# navx_micro_1_0.net
KiCad netlist of a schematic drawn in EAGLE
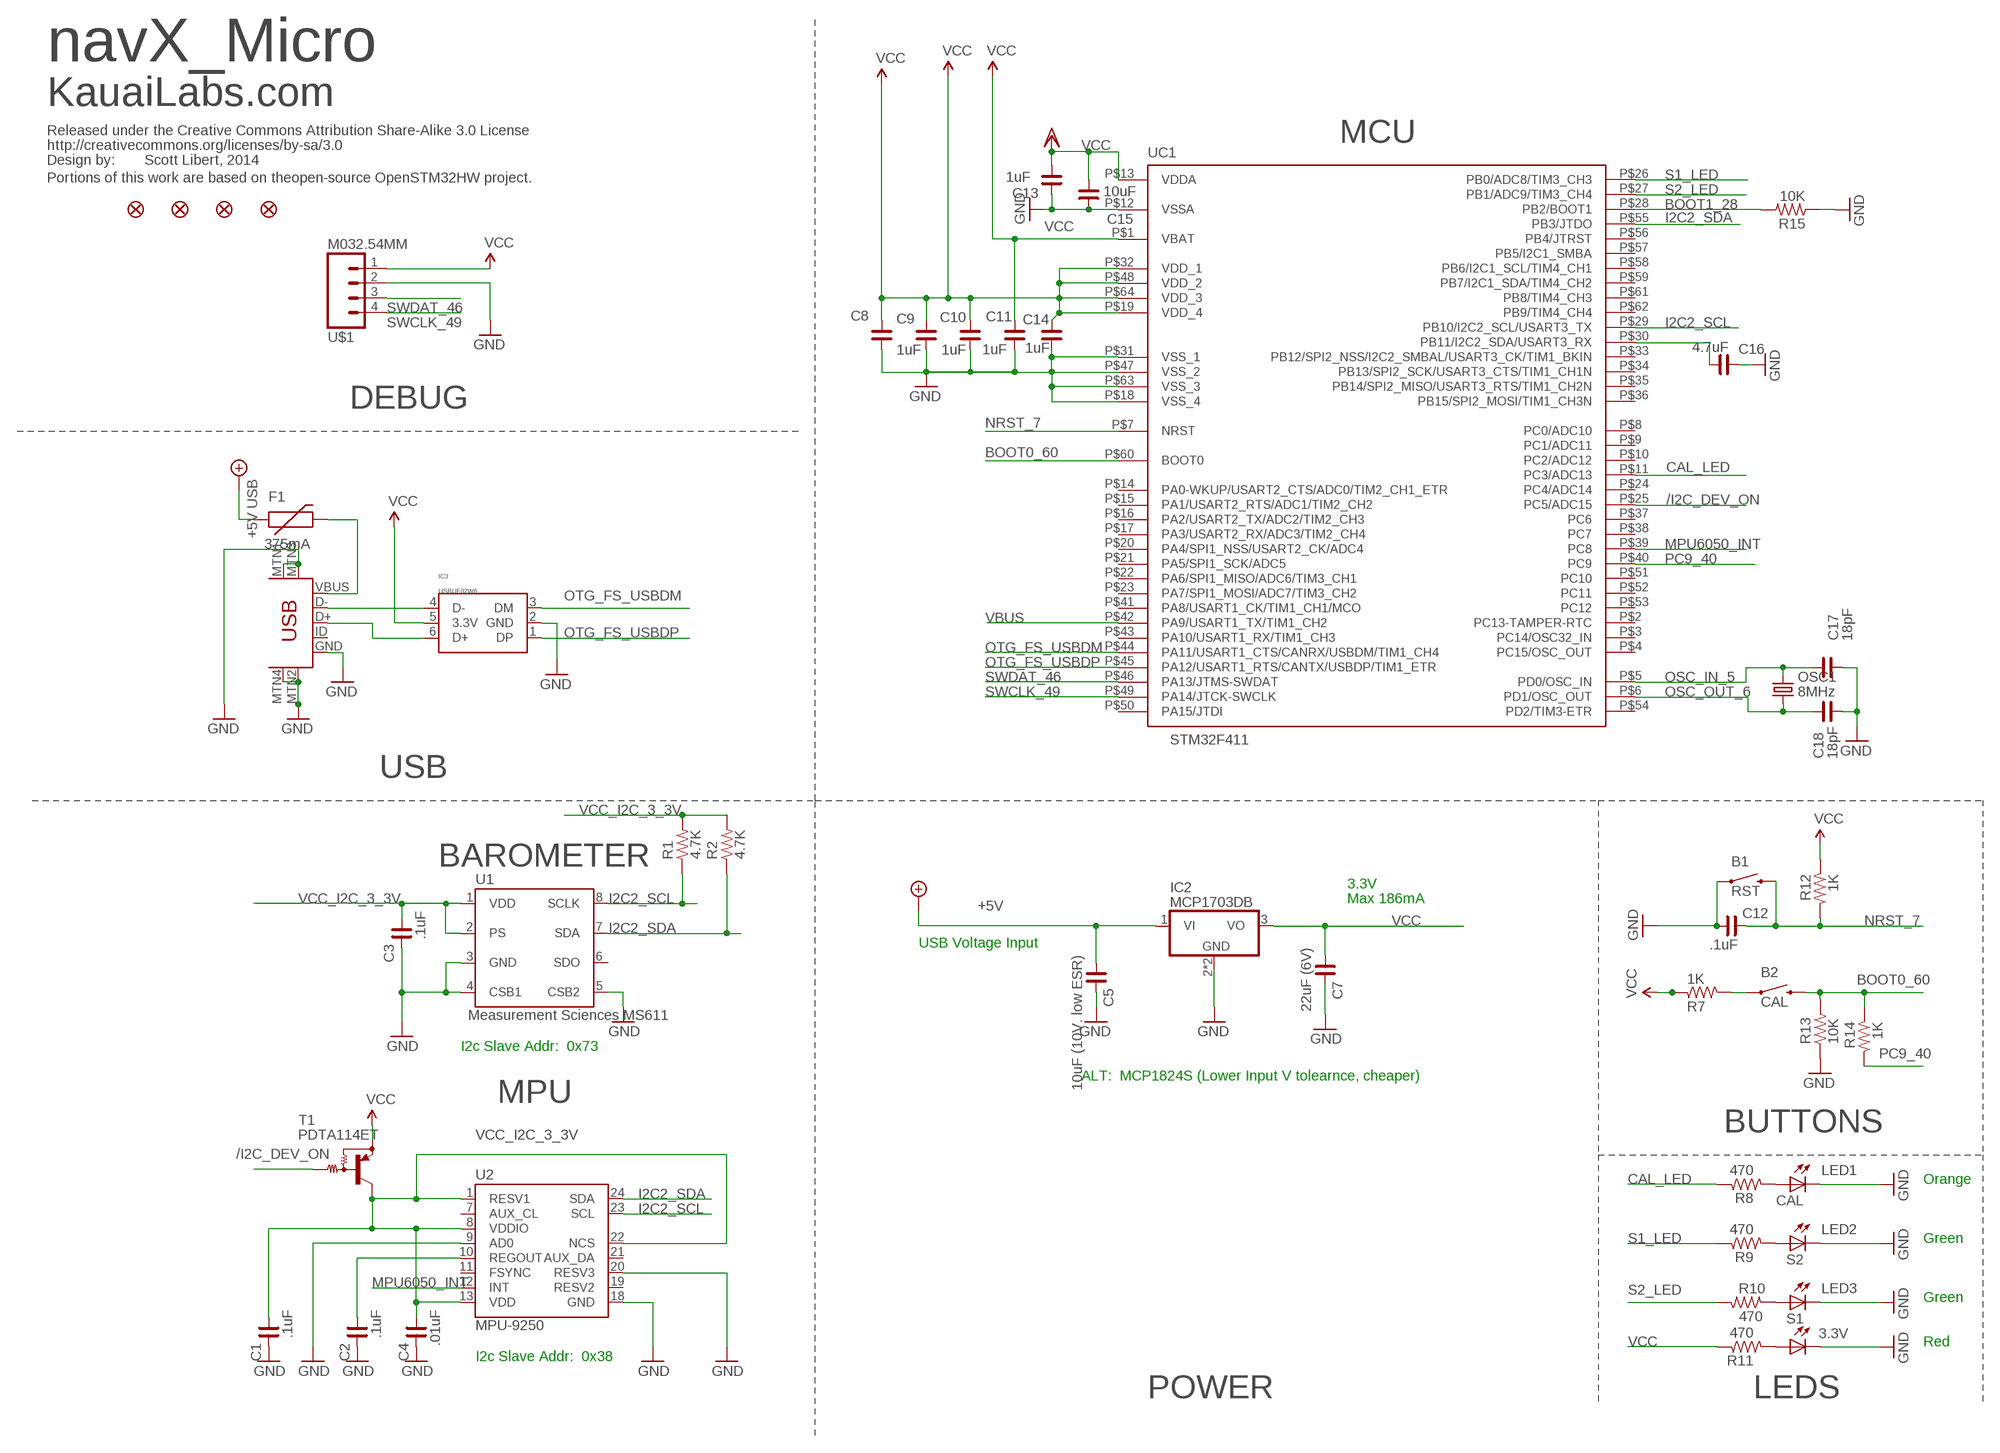
[diagram p0: schematic, sheet 1]

(export (version "E")
  (design (tool "Eeschema 10.0.6"))
  (components
    (comp (ref "B1")
      (value "RST")
      (footprint "eagle-import:TACTILE-SWITCH-1101NE")
      (libsource (lib "eagle-import") (part "SWITCH-MOMENTARY-2-SMD-1101NE"))
    )
    (comp (ref "B2")
      (value "CAL")
      (footprint "eagle-import:TACTILE-SWITCH-1101NE")
      (libsource (lib "eagle-import") (part "SWITCH-MOMENTARY-2-SMD-1101NE"))
    )
    (comp (ref "C1")
      (value ".1uF")
      (footprint "eagle-import:C0603")
      (libsource (lib "eagle-import") (part "C_0603"))
    )
    (comp (ref "C2")
      (value ".1uF")
      (footprint "eagle-import:C0603")
      (libsource (lib "eagle-import") (part "C_0603"))
    )
    (comp (ref "C3")
      (value ".1uF")
      (footprint "eagle-import:C0603")
      (fields (field (name "DIGIKEY_PART_NUMBER") "399-1096-1-ND"))
      (libsource (lib "eagle-import") (part "C_0603"))
    )
    (comp (ref "C4")
      (value ".01uF")
      (footprint "eagle-import:C0603")
      (libsource (lib "eagle-import") (part "C_0603"))
    )
    (comp (ref "C5")
      (value "10uF (10V. low ESR)")
      (footprint "eagle-import:C0805")
      (fields (field (name "DIGIKEY_PART_NUMBER") "399-1158-1-ND"))
      (libsource (lib "eagle-import") (part "C_0805"))
    )
    (comp (ref "C7")
      (value "22uF (6V)")
      (footprint "eagle-import:C0805")
      (fields (field (name "DIGIKEY_PART_NUMBER") "399-1158-1-ND"))
      (libsource (lib "eagle-import") (part "C_0805"))
    )
    (comp (ref "C8")
      (value "1uF")
      (footprint "eagle-import:C0603")
      (fields (field (name "DIGIKEY_PART_NUMBER") "399-3118-1-ND"))
      (libsource (lib "eagle-import") (part "C_0603"))
    )
    (comp (ref "C9")
      (value "1uF")
      (footprint "eagle-import:C0603")
      (libsource (lib "eagle-import") (part "C_0603"))
    )
    (comp (ref "C10")
      (value "1uF")
      (footprint "eagle-import:C0603")
      (libsource (lib "eagle-import") (part "C_0603"))
    )
    (comp (ref "C11")
      (value "1uF")
      (footprint "eagle-import:C0603")
      (libsource (lib "eagle-import") (part "C_0603"))
    )
    (comp (ref "C12")
      (value ".1uF")
      (footprint "eagle-import:C0603")
      (libsource (lib "eagle-import") (part "C_0603"))
    )
    (comp (ref "C13")
      (value "1uF")
      (footprint "eagle-import:C0603")
      (libsource (lib "eagle-import") (part "C_0603"))
    )
    (comp (ref "C14")
      (value "1uF")
      (footprint "eagle-import:C0603")
      (libsource (lib "eagle-import") (part "C_0603"))
    )
    (comp (ref "C15")
      (value "10uF")
      (footprint "eagle-import:C0805")
      (libsource (lib "eagle-import") (part "C_0805"))
    )
    (comp (ref "C16")
      (value "4.7uF")
      (footprint "eagle-import:C0603")
      (libsource (lib "eagle-import") (part "C_0603"))
    )
    (comp (ref "C17")
      (value "18pF")
      (footprint "eagle-import:C0603")
      (libsource (lib "eagle-import") (part "C_0603"))
    )
    (comp (ref "C18")
      (value "18pF")
      (footprint "eagle-import:C0603")
      (libsource (lib "eagle-import") (part "C_0603"))
    )
    (comp (ref "F1")
      (value "375mA")
      (footprint "eagle-import:0603")
      (libsource (lib "eagle-import") (part "PTC0603"))
    )
    (comp (ref "IC2")
      (value "MCP1703DB")
      (footprint "eagle-import:MCP1703DB")
      (fields (field (name "DIGIKEY_PART_NUMBER") "MCP1703T-3302E/DBCT-ND"))
      (libsource (lib "eagle-import") (part "MCP1703DB"))
    )
    (comp (ref "IC3")
      (value "USBUF02W6")
      (footprint "eagle-import:SC70-6")
      (fields (field (name "DIGIKEY_PART_NUMBER") "497-3743-1-ND"))
      (libsource (lib "eagle-import") (part "USBUF02W6"))
    )
    (comp (ref "JP21")
      (value "FIDUCIAL1X2")
      (footprint "eagle-import:FIDUCIAL-1X2")
      (libsource (lib "eagle-import") (part "FIDUCIAL1X2"))
    )
    (comp (ref "JP22")
      (value "FIDUCIAL1X2")
      (footprint "eagle-import:FIDUCIAL-1X2")
      (libsource (lib "eagle-import") (part "FIDUCIAL1X2"))
    )
    (comp (ref "JP23")
      (value "FIDUCIAL1X2")
      (footprint "eagle-import:FIDUCIAL-1X2")
      (libsource (lib "eagle-import") (part "FIDUCIAL1X2"))
    )
    (comp (ref "JP24")
      (value "FIDUCIAL1X2")
      (footprint "eagle-import:FIDUCIAL-1X2")
      (libsource (lib "eagle-import") (part "FIDUCIAL1X2"))
    )
    (comp (ref "LED1")
      (value "CAL")
      (footprint "eagle-import:CHIP-LED0603")
      (libsource (lib "eagle-import") (part "LEDCHIP-LED0603"))
    )
    (comp (ref "LED2")
      (value "S2")
      (footprint "eagle-import:CHIP-LED0603")
      (libsource (lib "eagle-import") (part "LEDCHIP-LED0603"))
    )
    (comp (ref "LED3")
      (value "S1")
      (footprint "eagle-import:CHIP-LED0603")
      (libsource (lib "eagle-import") (part "LEDCHIP-LED0603"))
    )
    (comp (ref "LED4")
      (value "3.3V")
      (footprint "eagle-import:CHIP-LED0603")
      (libsource (lib "eagle-import") (part "LEDCHIP-LED0603"))
    )
    (comp (ref "LICENSE_TEXT")
      (value "CREATIVE_COMMONS")
      (footprint "eagle-import:CREATIVE_COMMONS")
      (libsource (lib "eagle-import") (part "CREATIVE_COMMONS"))
    )
    (comp (ref "OSC1")
      (value "8MHz")
      (footprint "eagle-import:CRYSTAL-SMD-5X3")
      (libsource (lib "eagle-import") (part "CRYSTAL5X3"))
    )
    (comp (ref "R1")
      (value "4.7K")
      (footprint "eagle-import:R0603")
      (libsource (lib "eagle-import") (part "R_0603"))
    )
    (comp (ref "R2")
      (value "4.7K")
      (footprint "eagle-import:R0603")
      (libsource (lib "eagle-import") (part "R_0603"))
    )
    (comp (ref "R7")
      (value "1K")
      (footprint "eagle-import:R0603")
      (libsource (lib "eagle-import") (part "R_0603"))
    )
    (comp (ref "R8")
      (value "470")
      (footprint "eagle-import:R0603")
      (libsource (lib "eagle-import") (part "R_0603"))
    )
    (comp (ref "R9")
      (value "470")
      (footprint "eagle-import:R0603")
      (libsource (lib "eagle-import") (part "R_0603"))
    )
    (comp (ref "R10")
      (value "470")
      (footprint "eagle-import:R0603")
      (libsource (lib "eagle-import") (part "R_0603"))
    )
    (comp (ref "R11")
      (value "470")
      (footprint "eagle-import:R0603")
      (libsource (lib "eagle-import") (part "R_0603"))
    )
    (comp (ref "R12")
      (value "1K")
      (footprint "eagle-import:R0603")
      (libsource (lib "eagle-import") (part "R_0603"))
    )
    (comp (ref "R13")
      (value "10K")
      (footprint "eagle-import:R0603")
      (libsource (lib "eagle-import") (part "R_0603"))
    )
    (comp (ref "R14")
      (value "1K")
      (footprint "eagle-import:R0603")
      (libsource (lib "eagle-import") (part "R_0603"))
    )
    (comp (ref "R15")
      (value "10K")
      (footprint "eagle-import:R0603")
      (libsource (lib "eagle-import") (part "R_0603"))
    )
    (comp (ref "T1")
      (value "PDTA114ET")
      (footprint "eagle-import:SOT23-3")
      (libsource (lib "eagle-import") (part "PNP-DRIVERSOT23-3"))
    )
    (comp (ref "U$1")
      (value "M032.54MM")
      (footprint "eagle-import:1X04_NO_SILK")
      (libsource (lib "eagle-import") (part "M041X04_NO_SILK"))
    )
    (comp (ref "U1")
      (value "Measurement Sciences MS611")
      (footprint "eagle-import:MS5611")
      (fields (field (name "DIGIKEY_PART_NUMBER") "MPL115A2-ND"))
      (libsource (lib "eagle-import") (part "MS5611"))
    )
    (comp (ref "U2")
      (value "MPU-9250")
      (footprint "eagle-import:QFN24_3MM_INVENSENSE")
      (fields
        (field (name "DIGIKEY_PART_NUMBER") "1428-1019-1-ND")
        (field (name "MANUFACTURER") "INVENSENSE")
      )
      (libsource (lib "eagle-import") (part "MPU-9250"))
    )
    (comp (ref "UC1")
      (value "STM32F411")
      (footprint "eagle-import:TQFP-10X10-64")
      (fields (field (name "DIGIKEY_PART_NUMBER") "497-11154-ND"))
      (libsource (lib "eagle-import") (part "STM32F103"))
    )
    (comp (ref "USB")
      (value "Mini-USB")
      (footprint "eagle-import:USB-MINIB")
      (fields (field (name "DIGIKEY_PART_NUMBER") "151-1206-1-ND"))
      (libsource (lib "eagle-import") (part "USB-MINIB-5PIN"))
    )
  )
  (nets
    (net (code "1") (name "+5V USB") (class "Default")
      (node (ref "C5") (pin "1") (pinfunction "1_1") (pintype "passive"))
      (node (ref "F1") (pin "1") (pinfunction "1_1") (pintype "bidirectional"))
      (node (ref "IC2") (pin "1") (pinfunction "VI_1") (pintype "input"))
    )
    (net (code "2") (name "/BOOT0_60") (class "Default")
      (node (ref "B2") (pin "P$2") (pinfunction "2_P$2") (pintype "passive"))
      (node (ref "R13") (pin "2") (pinfunction "2_2") (pintype "passive"))
      (node (ref "R14") (pin "1") (pinfunction "1_1") (pintype "passive"))
      (node (ref "UC1") (pin "P$60") (pinfunction "BOOT0_P$60") (pintype "bidirectional"))
    )
    (net (code "3") (name "/BOOT1_28") (class "Default")
      (node (ref "R15") (pin "2") (pinfunction "2_2") (pintype "passive"))
      (node (ref "UC1") (pin "P$28") (pinfunction "PB2/BOOT1_P$28") (pintype "bidirectional"))
    )
    (net (code "4") (name "/CAL_LED") (class "Default")
      (node (ref "R8") (pin "1") (pinfunction "1_1") (pintype "passive"))
      (node (ref "UC1") (pin "P$11") (pinfunction "PC3/ADC13_P$11") (pintype "bidirectional"))
    )
    (net (code "5") (name "/I2C2_SCL") (class "Default")
      (node (ref "R1") (pin "1") (pinfunction "1_1") (pintype "passive"))
      (node (ref "U1") (pin "8") (pinfunction "SCLK_8") (pintype "bidirectional"))
      (node (ref "U2") (pin "23") (pinfunction "SCL_23") (pintype "bidirectional"))
      (node (ref "UC1") (pin "P$29") (pinfunction "PB10/I2C2_SCL/USART3_TX_P$29") (pintype "bidirectional"))
    )
    (net (code "6") (name "/I2C2_SDA") (class "Default")
      (node (ref "R2") (pin "1") (pinfunction "1_1") (pintype "passive"))
      (node (ref "U1") (pin "7") (pinfunction "SDA_7") (pintype "bidirectional"))
      (node (ref "U2") (pin "24") (pinfunction "SDA_24") (pintype "bidirectional"))
      (node (ref "UC1") (pin "P$55") (pinfunction "PB3/JTDO_P$55") (pintype "bidirectional"))
    )
    (net (code "7") (name "/MPU6050_INT") (class "Default")
      (node (ref "U2") (pin "12") (pinfunction "INT_12") (pintype "bidirectional"))
      (node (ref "UC1") (pin "P$39") (pinfunction "PC8_P$39") (pintype "bidirectional"))
    )
    (net (code "8") (name "/NRST_7") (class "Default")
      (node (ref "B1") (pin "P$2") (pinfunction "2_P$2") (pintype "passive"))
      (node (ref "C12") (pin "2") (pinfunction "2_2") (pintype "passive"))
      (node (ref "R12") (pin "2") (pinfunction "2_2") (pintype "passive"))
      (node (ref "UC1") (pin "P$7") (pinfunction "NRST_P$7") (pintype "bidirectional"))
    )
    (net (code "9") (name "/OSC_IN_5") (class "Default")
      (node (ref "C17") (pin "2") (pinfunction "2_2") (pintype "passive"))
      (node (ref "OSC1") (pin "3") (pinfunction "2_3") (pintype "passive"))
      (node (ref "UC1") (pin "P$5") (pinfunction "PD0/OSC_IN_P$5") (pintype "bidirectional"))
    )
    (net (code "10") (name "/OSC_OUT_6") (class "Default")
      (node (ref "C18") (pin "2") (pinfunction "2_2") (pintype "passive"))
      (node (ref "OSC1") (pin "1") (pinfunction "1_1") (pintype "passive"))
      (node (ref "UC1") (pin "P$6") (pinfunction "PD1/OSC_OUT_P$6") (pintype "bidirectional"))
    )
    (net (code "11") (name "/OTG_FS_USBDM") (class "Default")
      (node (ref "IC3") (pin "3") (pinfunction "DM_3") (pintype "bidirectional"))
      (node (ref "UC1") (pin "P$44") (pinfunction "PA11/USART1_CTS/CANRX/USBDM/TIM1_CH4_P$44") (pintype "bidirectional"))
    )
    (net (code "12") (name "/OTG_FS_USBDP") (class "Default")
      (node (ref "IC3") (pin "1") (pinfunction "DP_1") (pintype "bidirectional"))
      (node (ref "UC1") (pin "P$45") (pinfunction "PA12/USART1_RTS/CANTX/USBDP/TIM1_ETR_P$45") (pintype "bidirectional"))
    )
    (net (code "13") (name "/PC9_40") (class "Default")
      (node (ref "R14") (pin "2") (pinfunction "2_2") (pintype "passive"))
      (node (ref "UC1") (pin "P$40") (pinfunction "PC9_P$40") (pintype "bidirectional"))
    )
    (net (code "14") (name "/S1_LED") (class "Default")
      (node (ref "R9") (pin "1") (pinfunction "1_1") (pintype "passive"))
      (node (ref "UC1") (pin "P$26") (pinfunction "PB0/ADC8/TIM3_CH3_P$26") (pintype "bidirectional"))
    )
    (net (code "15") (name "/S2_LED") (class "Default")
      (node (ref "R10") (pin "2") (pinfunction "2_2") (pintype "passive"))
      (node (ref "UC1") (pin "P$27") (pinfunction "PB1/ADC9/TIM3_CH4_P$27") (pintype "bidirectional"))
    )
    (net (code "16") (name "/SWCLK_49") (class "Default")
      (node (ref "U$1") (pin "4") (pinfunction "4_4") (pintype "passive"))
      (node (ref "UC1") (pin "P$49") (pinfunction "PA14/JTCK-SWCLK_P$49") (pintype "bidirectional"))
    )
    (net (code "17") (name "/SWDAT_46") (class "Default")
      (node (ref "U$1") (pin "3") (pinfunction "3_3") (pintype "passive"))
      (node (ref "UC1") (pin "P$46") (pinfunction "PA13/JTMS-SWDAT_P$46") (pintype "bidirectional"))
    )
    (net (code "18") (name "/VBUS") (class "Default")
      (node (ref "F1") (pin "2") (pinfunction "2_2") (pintype "bidirectional"))
      (node (ref "UC1") (pin "P$42") (pinfunction "PA9/USART1_TX/TIM1_CH2_P$42") (pintype "bidirectional"))
      (node (ref "USB") (pin "VBUS") (pinfunction "VBUS_VBUS") (pintype "bidirectional"))
    )
    (net (code "19") (name "/VCC_I2C_3_3V") (class "Default")
      (node (ref "C1") (pin "1") (pinfunction "1_1") (pintype "passive"))
      (node (ref "C3") (pin "1") (pinfunction "1_1") (pintype "passive"))
      (node (ref "C4") (pin "1") (pinfunction "1_1") (pintype "passive"))
      (node (ref "R1") (pin "2") (pinfunction "2_2") (pintype "passive"))
      (node (ref "R2") (pin "2") (pinfunction "2_2") (pintype "passive"))
      (node (ref "T1") (pin "3") (pinfunction "C_3") (pintype "passive"))
      (node (ref "U1") (pin "1") (pinfunction "VDD_1") (pintype "bidirectional"))
      (node (ref "U1") (pin "2") (pinfunction "PS_2") (pintype "bidirectional"))
      (node (ref "U2") (pin "1") (pinfunction "RESV1_1") (pintype "bidirectional"))
      (node (ref "U2") (pin "13") (pinfunction "VDD_13") (pintype "bidirectional"))
      (node (ref "U2") (pin "22") (pinfunction "NCS_22") (pintype "bidirectional"))
      (node (ref "U2") (pin "8") (pinfunction "VDDIO_8") (pintype "bidirectional"))
    )
    (net (code "20") (name "/{slash}I2C_DEV_ON") (class "Default")
      (node (ref "T1") (pin "1") (pinfunction "B_1") (pintype "passive"))
      (node (ref "UC1") (pin "P$25") (pinfunction "PC5/ADC15_P$25") (pintype "bidirectional"))
    )
    (net (code "21") (name "GND") (class "Default")
      (node (ref "B1") (pin "P$1") (pinfunction "1_P$1") (pintype "passive"))
      (node (ref "C1") (pin "2") (pinfunction "2_2") (pintype "passive"))
      (node (ref "C10") (pin "1") (pinfunction "1_1") (pintype "passive"))
      (node (ref "C11") (pin "1") (pinfunction "1_1") (pintype "passive"))
      (node (ref "C12") (pin "1") (pinfunction "1_1") (pintype "passive"))
      (node (ref "C13") (pin "1") (pinfunction "1_1") (pintype "passive"))
      (node (ref "C14") (pin "1") (pinfunction "1_1") (pintype "passive"))
      (node (ref "C15") (pin "2") (pinfunction "2_2") (pintype "passive"))
      (node (ref "C16") (pin "1") (pinfunction "1_1") (pintype "passive"))
      (node (ref "C17") (pin "1") (pinfunction "1_1") (pintype "passive"))
      (node (ref "C18") (pin "1") (pinfunction "1_1") (pintype "passive"))
      (node (ref "C2") (pin "2") (pinfunction "2_2") (pintype "passive"))
      (node (ref "C3") (pin "2") (pinfunction "2_2") (pintype "passive"))
      (node (ref "C4") (pin "2") (pinfunction "2_2") (pintype "passive"))
      (node (ref "C5") (pin "2") (pinfunction "2_2") (pintype "passive"))
      (node (ref "C7") (pin "2") (pinfunction "2_2") (pintype "passive"))
      (node (ref "C8") (pin "1") (pinfunction "1_1") (pintype "passive"))
      (node (ref "C9") (pin "1") (pinfunction "1_1") (pintype "passive"))
      (node (ref "IC2") (pin "2") (pinfunction "GND_2") (pintype "passive"))
      (node (ref "IC2") (pin "4") (pinfunction "GND_4") (pintype "passive"))
      (node (ref "IC3") (pin "2") (pinfunction "GND_2") (pintype "bidirectional"))
      (node (ref "LED1") (pin "C") (pinfunction "C_C") (pintype "passive"))
      (node (ref "LED2") (pin "C") (pinfunction "C_C") (pintype "passive"))
      (node (ref "LED3") (pin "C") (pinfunction "C_C") (pintype "passive"))
      (node (ref "LED4") (pin "C") (pinfunction "C_C") (pintype "passive"))
      (node (ref "R13") (pin "1") (pinfunction "1_1") (pintype "passive"))
      (node (ref "R15") (pin "1") (pinfunction "1_1") (pintype "passive"))
      (node (ref "U$1") (pin "2") (pinfunction "2_2") (pintype "passive"))
      (node (ref "U1") (pin "3") (pinfunction "GND_3") (pintype "bidirectional"))
      (node (ref "U1") (pin "4") (pinfunction "CSB1_4") (pintype "bidirectional"))
      (node (ref "U1") (pin "5") (pinfunction "CSB2_5") (pintype "bidirectional"))
      (node (ref "U2") (pin "18") (pinfunction "GND_18") (pintype "bidirectional"))
      (node (ref "U2") (pin "20") (pinfunction "RESV3_20") (pintype "bidirectional"))
      (node (ref "U2") (pin "9") (pinfunction "AD0_9") (pintype "bidirectional"))
      (node (ref "UC1") (pin "P$12") (pinfunction "VSSA_P$12") (pintype "power_in"))
      (node (ref "UC1") (pin "P$18") (pinfunction "VSS_4_P$18") (pintype "power_in"))
      (node (ref "UC1") (pin "P$31") (pinfunction "VSS_1_P$31") (pintype "power_in"))
      (node (ref "UC1") (pin "P$47") (pinfunction "VSS_2_P$47") (pintype "power_in"))
      (node (ref "UC1") (pin "P$63") (pinfunction "VSS_3_P$63") (pintype "power_in"))
      (node (ref "USB") (pin "GND") (pinfunction "GND_GND") (pintype "bidirectional"))
      (node (ref "USB") (pin "MTN1") (pinfunction "MTN2_MTN1") (pintype "bidirectional"))
      (node (ref "USB") (pin "MTN2") (pinfunction "MTN3_MTN2") (pintype "bidirectional"))
      (node (ref "USB") (pin "MTN3") (pinfunction "MTN1_MTN3") (pintype "bidirectional"))
      (node (ref "USB") (pin "MTN4") (pinfunction "MTN4_MTN4") (pintype "bidirectional"))
    )
    (net (code "22") (name "Net-(B2-1)") (class "Default")
      (node (ref "B2") (pin "P$1") (pinfunction "1_P$1") (pintype "passive"))
      (node (ref "R7") (pin "2") (pinfunction "2_2") (pintype "passive"))
    )
    (net (code "23") (name "Net-(IC3-D+)") (class "Default")
      (node (ref "IC3") (pin "6") (pinfunction "D+_6") (pintype "bidirectional"))
      (node (ref "USB") (pin "D+") (pinfunction "D+_D+") (pintype "bidirectional"))
    )
    (net (code "24") (name "Net-(IC3-D-)") (class "Default")
      (node (ref "IC3") (pin "4") (pinfunction "D-_4") (pintype "bidirectional"))
      (node (ref "USB") (pin "D-") (pinfunction "D-_D-") (pintype "bidirectional"))
    )
    (net (code "25") (name "Net-(LED1-PadA)") (class "Default")
      (node (ref "LED1") (pin "A") (pinfunction "A_A") (pintype "passive"))
      (node (ref "R8") (pin "2") (pinfunction "2_2") (pintype "passive"))
    )
    (net (code "26") (name "Net-(LED2-PadA)") (class "Default")
      (node (ref "LED2") (pin "A") (pinfunction "A_A") (pintype "passive"))
      (node (ref "R9") (pin "2") (pinfunction "2_2") (pintype "passive"))
    )
    (net (code "27") (name "Net-(LED3-PadA)") (class "Default")
      (node (ref "LED3") (pin "A") (pinfunction "A_A") (pintype "passive"))
      (node (ref "R10") (pin "1") (pinfunction "1_1") (pintype "passive"))
    )
    (net (code "28") (name "Net-(LED4-PadA)") (class "Default")
      (node (ref "LED4") (pin "A") (pinfunction "A_A") (pintype "passive"))
      (node (ref "R11") (pin "2") (pinfunction "2_2") (pintype "passive"))
    )
    (net (code "29") (name "Net-(U2-REGOUT)") (class "Default")
      (node (ref "C2") (pin "1") (pinfunction "1_1") (pintype "passive"))
      (node (ref "U2") (pin "10") (pinfunction "REGOUT_10") (pintype "bidirectional"))
    )
    (net (code "30") (name "Net-(UC1-PB11{slash}I2C2_SDA{slash}USART3_RX)") (class "Default")
      (node (ref "C16") (pin "2") (pinfunction "2_2") (pintype "passive"))
      (node (ref "UC1") (pin "P$30") (pinfunction "PB11/I2C2_SDA/USART3_RX_P$30") (pintype "bidirectional"))
    )
    (net (code "31") (name "VCC") (class "Default")
      (node (ref "C10") (pin "2") (pinfunction "2_2") (pintype "passive"))
      (node (ref "C11") (pin "2") (pinfunction "2_2") (pintype "passive"))
      (node (ref "C13") (pin "2") (pinfunction "2_2") (pintype "passive"))
      (node (ref "C14") (pin "2") (pinfunction "2_2") (pintype "passive"))
      (node (ref "C15") (pin "1") (pinfunction "1_1") (pintype "passive"))
      (node (ref "C7") (pin "1") (pinfunction "1_1") (pintype "passive"))
      (node (ref "C8") (pin "2") (pinfunction "2_2") (pintype "passive"))
      (node (ref "C9") (pin "2") (pinfunction "2_2") (pintype "passive"))
      (node (ref "IC2") (pin "3") (pinfunction "VO_3") (pintype "passive"))
      (node (ref "IC3") (pin "5") (pinfunction "3.3V_5") (pintype "bidirectional"))
      (node (ref "R11") (pin "1") (pinfunction "1_1") (pintype "passive"))
      (node (ref "R12") (pin "1") (pinfunction "1_1") (pintype "passive"))
      (node (ref "R7") (pin "1") (pinfunction "1_1") (pintype "passive"))
      (node (ref "T1") (pin "2") (pinfunction "E_2") (pintype "passive"))
      (node (ref "U$1") (pin "1") (pinfunction "1_1") (pintype "passive"))
      (node (ref "UC1") (pin "P$1") (pinfunction "VBAT_P$1") (pintype "power_in"))
      (node (ref "UC1") (pin "P$13") (pinfunction "VDDA_P$13") (pintype "power_in"))
      (node (ref "UC1") (pin "P$19") (pinfunction "VDD_4_P$19") (pintype "power_in"))
      (node (ref "UC1") (pin "P$32") (pinfunction "VDD_1_P$32") (pintype "power_in"))
      (node (ref "UC1") (pin "P$48") (pinfunction "VDD_2_P$48") (pintype "power_in"))
      (node (ref "UC1") (pin "P$64") (pinfunction "VDD_3_P$64") (pintype "power_in"))
    )
    (net (code "32") (name "unconnected-(U1-SDO-Pad6)") (class "Default")
      (node (ref "U1") (pin "6") (pinfunction "SDO_6") (pintype "bidirectional"))
    )
    (net (code "33") (name "unconnected-(U2-AUX_CL-Pad7)") (class "Default")
      (node (ref "U2") (pin "7") (pinfunction "AUX_CL_7") (pintype "bidirectional"))
    )
    (net (code "34") (name "unconnected-(U2-AUX_DA-Pad21)") (class "Default")
      (node (ref "U2") (pin "21") (pinfunction "AUX_DA_21") (pintype "bidirectional"))
    )
    (net (code "35") (name "unconnected-(U2-FSYNC-Pad11)") (class "Default")
      (node (ref "U2") (pin "11") (pinfunction "FSYNC_11") (pintype "bidirectional"))
    )
    (net (code "36") (name "unconnected-(U2-RESV2-Pad19)") (class "Default")
      (node (ref "U2") (pin "19") (pinfunction "RESV2_19") (pintype "bidirectional"))
    )
    (net (code "37") (name "unconnected-(UC1-PA0-WKUP{slash}USART2_CTS{slash}ADC0{slash}TIM2_CH1_ETR-PadP$14)") (class "Default")
      (node (ref "UC1") (pin "P$14") (pinfunction "PA0-WKUP/USART2_CTS/ADC0/TIM2_CH1_ETR_P$14") (pintype "bidirectional"))
    )
    (net (code "38") (name "unconnected-(UC1-PA1{slash}USART2_RTS{slash}ADC1{slash}TIM2_CH2-PadP$15)") (class "Default")
      (node (ref "UC1") (pin "P$15") (pinfunction "PA1/USART2_RTS/ADC1/TIM2_CH2_P$15") (pintype "bidirectional"))
    )
    (net (code "39") (name "unconnected-(UC1-PA2{slash}USART2_TX{slash}ADC2{slash}TIM2_CH3-PadP$16)") (class "Default")
      (node (ref "UC1") (pin "P$16") (pinfunction "PA2/USART2_TX/ADC2/TIM2_CH3_P$16") (pintype "bidirectional"))
    )
    (net (code "40") (name "unconnected-(UC1-PA3{slash}USART2_RX{slash}ADC3{slash}TIM2_CH4-PadP$17)") (class "Default")
      (node (ref "UC1") (pin "P$17") (pinfunction "PA3/USART2_RX/ADC3/TIM2_CH4_P$17") (pintype "bidirectional"))
    )
    (net (code "41") (name "unconnected-(UC1-PA4{slash}SPI1_NSS{slash}USART2_CK{slash}ADC4-PadP$20)") (class "Default")
      (node (ref "UC1") (pin "P$20") (pinfunction "PA4/SPI1_NSS/USART2_CK/ADC4_P$20") (pintype "bidirectional"))
    )
    (net (code "42") (name "unconnected-(UC1-PA5{slash}SPI1_SCK{slash}ADC5-PadP$21)") (class "Default")
      (node (ref "UC1") (pin "P$21") (pinfunction "PA5/SPI1_SCK/ADC5_P$21") (pintype "bidirectional"))
    )
    (net (code "43") (name "unconnected-(UC1-PA6{slash}SPI1_MISO{slash}ADC6{slash}TIM3_CH1-PadP$22)") (class "Default")
      (node (ref "UC1") (pin "P$22") (pinfunction "PA6/SPI1_MISO/ADC6/TIM3_CH1_P$22") (pintype "bidirectional"))
    )
    (net (code "44") (name "unconnected-(UC1-PA7{slash}SPI1_MOSI{slash}ADC7{slash}TIM3_CH2-PadP$23)") (class "Default")
      (node (ref "UC1") (pin "P$23") (pinfunction "PA7/SPI1_MOSI/ADC7/TIM3_CH2_P$23") (pintype "bidirectional"))
    )
    (net (code "45") (name "unconnected-(UC1-PA8{slash}USART1_CK{slash}TIM1_CH1{slash}MCO-PadP$41)") (class "Default")
      (node (ref "UC1") (pin "P$41") (pinfunction "PA8/USART1_CK/TIM1_CH1/MCO_P$41") (pintype "bidirectional"))
    )
    (net (code "46") (name "unconnected-(UC1-PA10{slash}USART1_RX{slash}TIM1_CH3-PadP$43)") (class "Default")
      (node (ref "UC1") (pin "P$43") (pinfunction "PA10/USART1_RX/TIM1_CH3_P$43") (pintype "bidirectional"))
    )
    (net (code "47") (name "unconnected-(UC1-PA15{slash}JTDI-PadP$50)") (class "Default")
      (node (ref "UC1") (pin "P$50") (pinfunction "PA15/JTDI_P$50") (pintype "bidirectional"))
    )
    (net (code "48") (name "unconnected-(UC1-PB4{slash}JTRST-PadP$56)") (class "Default")
      (node (ref "UC1") (pin "P$56") (pinfunction "PB4/JTRST_P$56") (pintype "bidirectional"))
    )
    (net (code "49") (name "unconnected-(UC1-PB5{slash}I2C1_SMBA-PadP$57)") (class "Default")
      (node (ref "UC1") (pin "P$57") (pinfunction "PB5/I2C1_SMBA_P$57") (pintype "bidirectional"))
    )
    (net (code "50") (name "unconnected-(UC1-PB6{slash}I2C1_SCL{slash}TIM4_CH1-PadP$58)") (class "Default")
      (node (ref "UC1") (pin "P$58") (pinfunction "PB6/I2C1_SCL/TIM4_CH1_P$58") (pintype "bidirectional"))
    )
    (net (code "51") (name "unconnected-(UC1-PB7{slash}I2C1_SDA{slash}TIM4_CH2-PadP$59)") (class "Default")
      (node (ref "UC1") (pin "P$59") (pinfunction "PB7/I2C1_SDA/TIM4_CH2_P$59") (pintype "bidirectional"))
    )
    (net (code "52") (name "unconnected-(UC1-PB8{slash}TIM4_CH3-PadP$61)") (class "Default")
      (node (ref "UC1") (pin "P$61") (pinfunction "PB8/TIM4_CH3_P$61") (pintype "bidirectional"))
    )
    (net (code "53") (name "unconnected-(UC1-PB9{slash}TIM4_CH4-PadP$62)") (class "Default")
      (node (ref "UC1") (pin "P$62") (pinfunction "PB9/TIM4_CH4_P$62") (pintype "bidirectional"))
    )
    (net (code "54") (name "unconnected-(UC1-PB12{slash}SPI2_NSS{slash}I2C2_SMBAL{slash}USART3_CK{slash}TIM1_BKIN-PadP$33)") (class "Default")
      (node (ref "UC1") (pin "P$33") (pinfunction "PB12/SPI2_NSS/I2C2_SMBAL/USART3_CK/TIM1_BKIN_P$33") (pintype "bidirectional"))
    )
    (net (code "55") (name "unconnected-(UC1-PB13{slash}SPI2_SCK{slash}USART3_CTS{slash}TIM1_CH1N-PadP$34)") (class "Default")
      (node (ref "UC1") (pin "P$34") (pinfunction "PB13/SPI2_SCK/USART3_CTS/TIM1_CH1N_P$34") (pintype "bidirectional"))
    )
    (net (code "56") (name "unconnected-(UC1-PB14{slash}SPI2_MISO{slash}USART3_RTS{slash}TIM1_CH2N-PadP$35)") (class "Default")
      (node (ref "UC1") (pin "P$35") (pinfunction "PB14/SPI2_MISO/USART3_RTS/TIM1_CH2N_P$35") (pintype "bidirectional"))
    )
    (net (code "57") (name "unconnected-(UC1-PB15{slash}SPI2_MOSI{slash}TIM1_CH3N-PadP$36)") (class "Default")
      (node (ref "UC1") (pin "P$36") (pinfunction "PB15/SPI2_MOSI/TIM1_CH3N_P$36") (pintype "bidirectional"))
    )
    (net (code "58") (name "unconnected-(UC1-PC0{slash}ADC10-PadP$8)") (class "Default")
      (node (ref "UC1") (pin "P$8") (pinfunction "PC0/ADC10_P$8") (pintype "bidirectional"))
    )
    (net (code "59") (name "unconnected-(UC1-PC1{slash}ADC11-PadP$9)") (class "Default")
      (node (ref "UC1") (pin "P$9") (pinfunction "PC1/ADC11_P$9") (pintype "bidirectional"))
    )
    (net (code "60") (name "unconnected-(UC1-PC2{slash}ADC12-PadP$10)") (class "Default")
      (node (ref "UC1") (pin "P$10") (pinfunction "PC2/ADC12_P$10") (pintype "bidirectional"))
    )
    (net (code "61") (name "unconnected-(UC1-PC4{slash}ADC14-PadP$24)") (class "Default")
      (node (ref "UC1") (pin "P$24") (pinfunction "PC4/ADC14_P$24") (pintype "bidirectional"))
    )
    (net (code "62") (name "unconnected-(UC1-PC6-PadP$37)") (class "Default")
      (node (ref "UC1") (pin "P$37") (pinfunction "PC6_P$37") (pintype "bidirectional"))
    )
    (net (code "63") (name "unconnected-(UC1-PC7-PadP$38)") (class "Default")
      (node (ref "UC1") (pin "P$38") (pinfunction "PC7_P$38") (pintype "bidirectional"))
    )
    (net (code "64") (name "unconnected-(UC1-PC10-PadP$51)") (class "Default")
      (node (ref "UC1") (pin "P$51") (pinfunction "PC10_P$51") (pintype "bidirectional"))
    )
    (net (code "65") (name "unconnected-(UC1-PC11-PadP$52)") (class "Default")
      (node (ref "UC1") (pin "P$52") (pinfunction "PC11_P$52") (pintype "bidirectional"))
    )
    (net (code "66") (name "unconnected-(UC1-PC12-PadP$53)") (class "Default")
      (node (ref "UC1") (pin "P$53") (pinfunction "PC12_P$53") (pintype "bidirectional"))
    )
    (net (code "67") (name "unconnected-(UC1-PC13-TAMPER-RTC-PadP$2)") (class "Default")
      (node (ref "UC1") (pin "P$2") (pinfunction "PC13-TAMPER-RTC_P$2") (pintype "bidirectional"))
    )
    (net (code "68") (name "unconnected-(UC1-PC14{slash}OSC32_IN-PadP$3)") (class "Default")
      (node (ref "UC1") (pin "P$3") (pinfunction "PC14/OSC32_IN_P$3") (pintype "bidirectional"))
    )
    (net (code "69") (name "unconnected-(UC1-PC15{slash}OSC_OUT-PadP$4)") (class "Default")
      (node (ref "UC1") (pin "P$4") (pinfunction "PC15/OSC_OUT_P$4") (pintype "bidirectional"))
    )
    (net (code "70") (name "unconnected-(UC1-PD2{slash}TIM3-ETR-PadP$54)") (class "Default")
      (node (ref "UC1") (pin "P$54") (pinfunction "PD2/TIM3-ETR_P$54") (pintype "bidirectional"))
    )
    (net (code "71") (name "unconnected-(USB-PadID)") (class "Default")
      (node (ref "USB") (pin "ID") (pinfunction "ID_ID") (pintype "bidirectional"))
    )
  )
)
